# SpringReverbFront.net
KiCad netlist of a schematic drawn in EAGLE
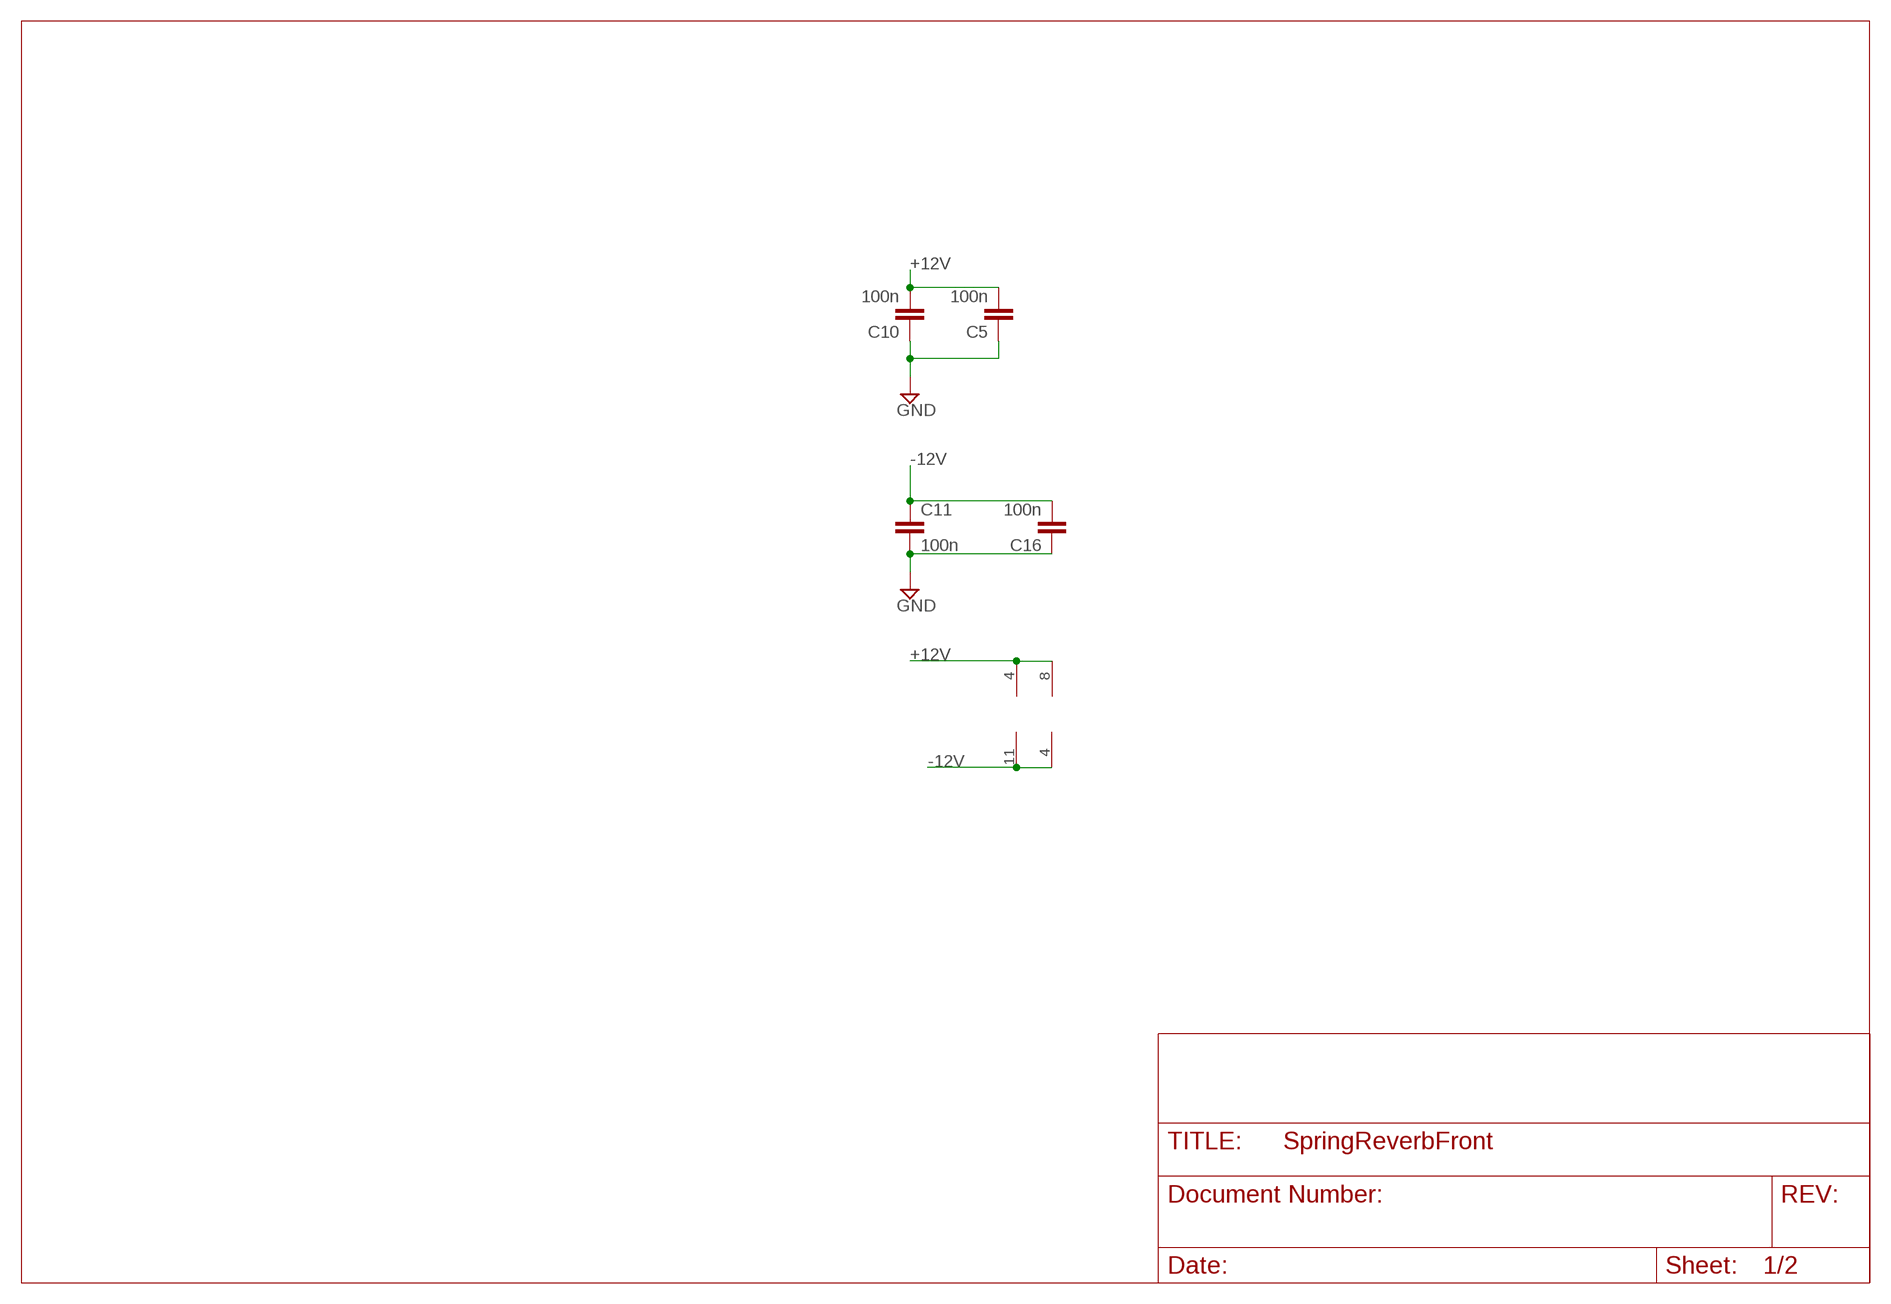
[diagram p0: schematic, sheet 1]
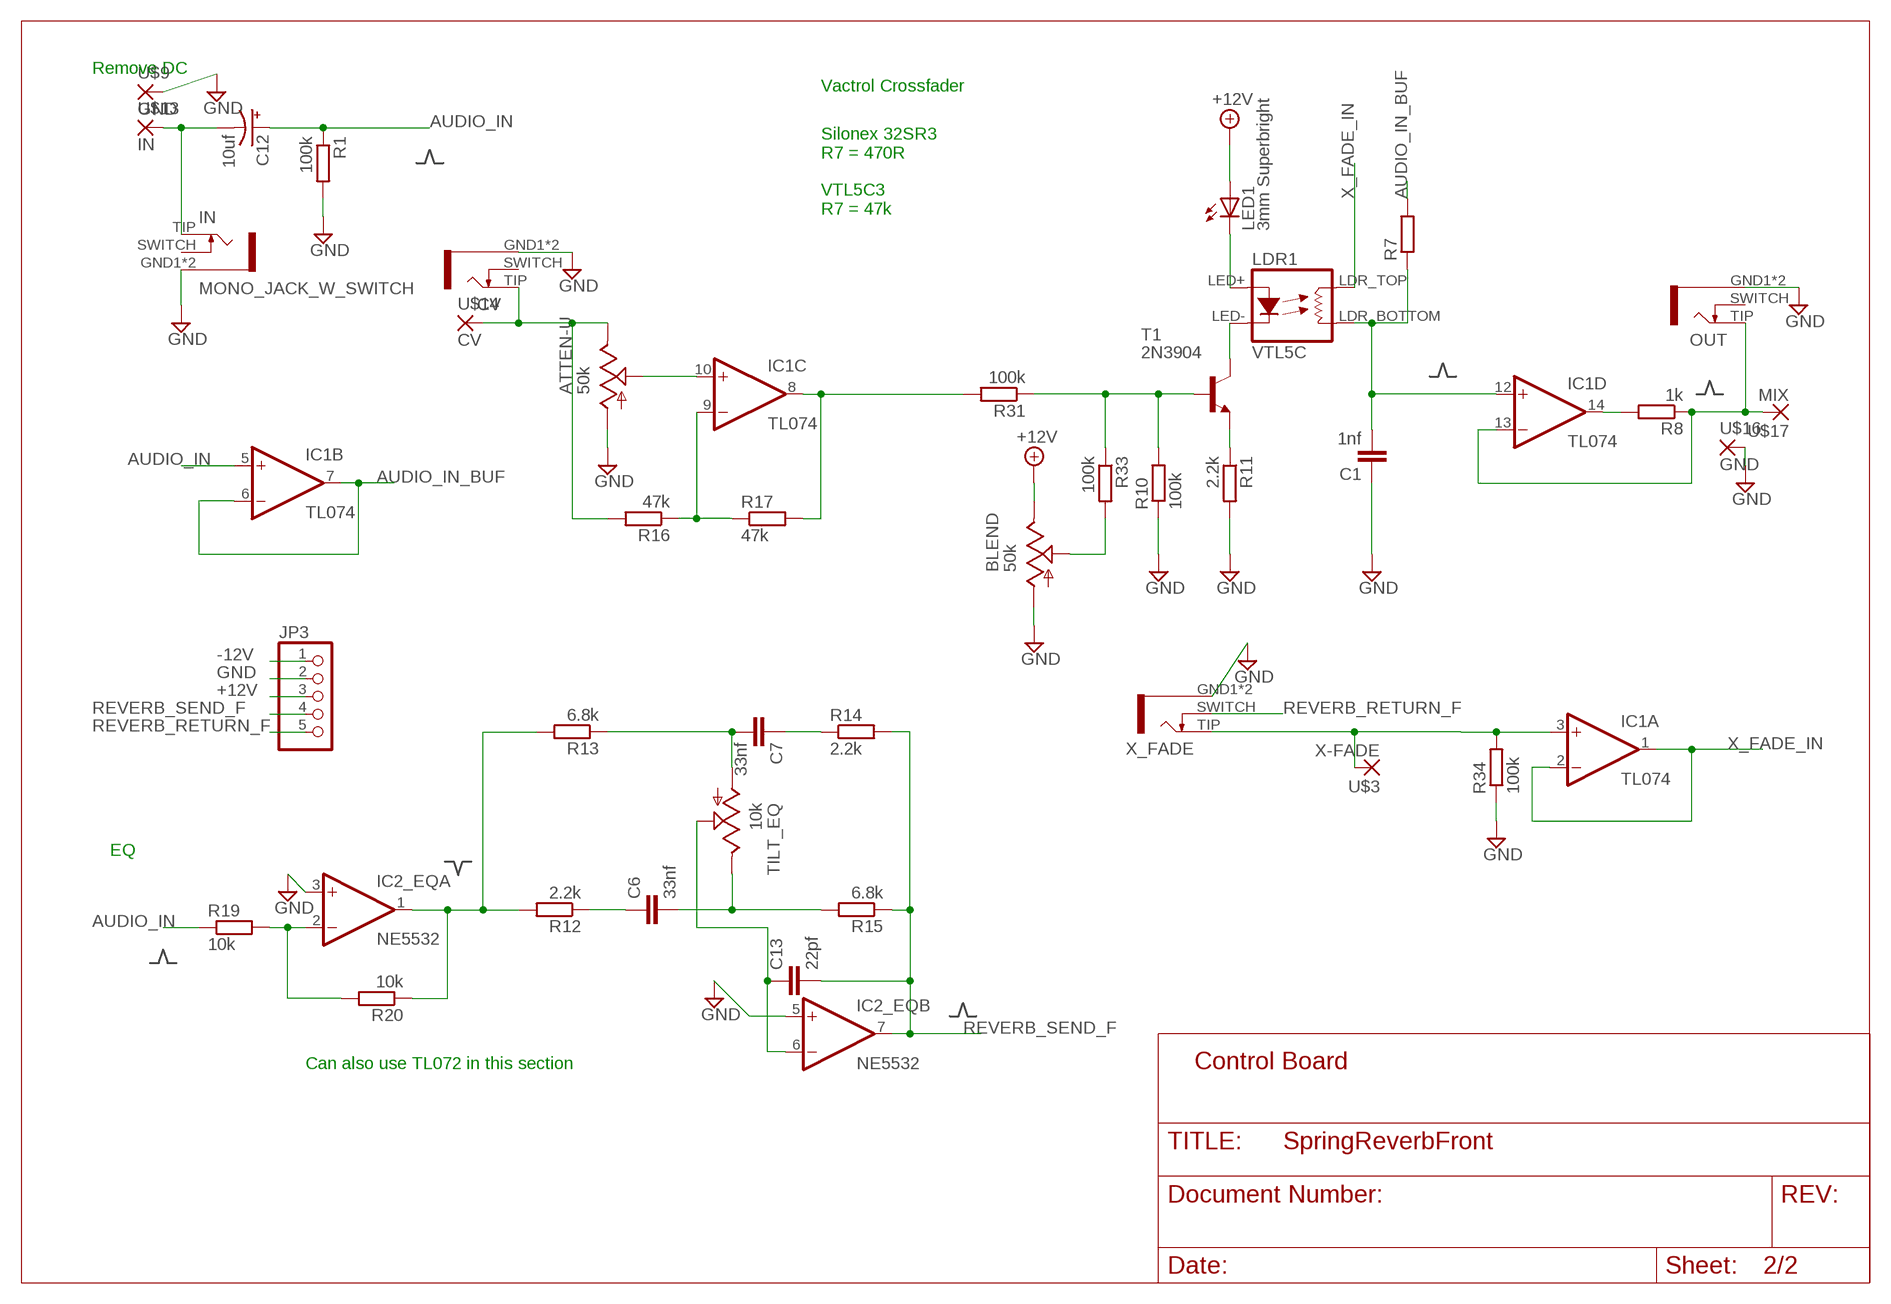
[diagram p1: schematic, sheet 2]

(export (version "E")
  (design (tool "Eeschema 10.0.6"))
  (components
    (comp (ref "ATTEN-U")
      (value "50k")
      (footprint "eagle-import:EVUF")
      (libsource (lib "eagle-import") (part "ALPHA-9MMAF2"))
    )
    (comp (ref "BLEND")
      (value "50k")
      (footprint "eagle-import:EVUF")
      (libsource (lib "eagle-import") (part "ALPHA-9MMAF2"))
    )
    (comp (ref "C1")
      (value "1nf")
      (footprint "eagle-import:C050-024X044")
      (libsource (lib "eagle-import") (part "C-EU050-024X044"))
    )
    (comp (ref "C6")
      (value "33nf")
      (footprint "eagle-import:C050-024X044")
      (libsource (lib "eagle-import") (part "C-EU050-024X044"))
    )
    (comp (ref "C7")
      (value "33nf")
      (footprint "eagle-import:C050-024X044")
      (libsource (lib "eagle-import") (part "C-EU050-024X044"))
    )
    (comp (ref "C12")
      (value "10uf")
      (footprint "eagle-import:050_020")
      (libsource (lib "eagle-import") (part "050"))
    )
    (comp (ref "C13")
      (value "22pf")
      (footprint "eagle-import:050X030_025")
      (libsource (lib "eagle-import") (part "050X030_0251"))
    )
    (comp (ref "CV")
      (value "MONO_JACK_W_SWITCH")
      (footprint "eagle-import:ERTHENVAR")
      (libsource (lib "eagle-import") (part "MONO_JACK_W_SWITCH"))
    )
    (comp (ref "IC1")
      (value "TL074")
      (footprint "eagle-import:DIL14")
      (libsource (lib "eagle-import") (part "TL074P"))
    )
    (comp (ref "IC2_EQ")
      (value "NE5532")
      (footprint "eagle-import:DIL08")
      (libsource (lib "eagle-import") (part "TL072P"))
    )
    (comp (ref "IN")
      (value "MONO_JACK_W_SWITCH")
      (footprint "eagle-import:ERTHENVAR")
      (libsource (lib "eagle-import") (part "MONO_JACK_W_SWITCH"))
    )
    (comp (ref "JP3")
      (value "PINHD-1X5")
      (footprint "eagle-import:1X05")
      (libsource (lib "eagle-import") (part "PINHD-1X5"))
    )
    (comp (ref "LDR1")
      (value "VTL5C")
      (footprint "eagle-import:VACTROL_COMPACT")
      (libsource (lib "eagle-import") (part "VACTROL_COMPACT"))
    )
    (comp (ref "LED1")
      (value "3mm Superbright")
      (footprint "eagle-import:LED3MM")
      (libsource (lib "eagle-import") (part "LED3MM"))
    )
    (comp (ref "OUT")
      (value "MONO_JACK_W_SWITCH")
      (footprint "eagle-import:ERTHENVAR")
      (libsource (lib "eagle-import") (part "MONO_JACK_W_SWITCH"))
    )
    (comp (ref "R1")
      (value "100k")
      (footprint "eagle-import:VERT-RESISTOR")
      (libsource (lib "eagle-import") (part "VERT-RESIST1"))
    )
    (comp (ref "R7")
      (value "R-EU_STANDARD_RESISTOR")
      (footprint "eagle-import:0207_10")
      (libsource (lib "eagle-import") (part "R-EU_STANDARD_RESISTOR"))
    )
    (comp (ref "R8")
      (value "1k")
      (footprint "eagle-import:0207_10")
      (libsource (lib "eagle-import") (part "R-EU_STANDARD_RESISTOR"))
    )
    (comp (ref "R10")
      (value "100k")
      (footprint "eagle-import:0207_10")
      (libsource (lib "eagle-import") (part "R-EU_STANDARD_RESISTOR"))
    )
    (comp (ref "R11")
      (value "2.2k")
      (footprint "eagle-import:0207_10")
      (libsource (lib "eagle-import") (part "R-EU_STANDARD_RESISTOR"))
    )
    (comp (ref "R12")
      (value "2.2k")
      (footprint "eagle-import:0207_10")
      (libsource (lib "eagle-import") (part "R-EU_STANDARD_RESISTOR"))
    )
    (comp (ref "R13")
      (value "6.8k")
      (footprint "eagle-import:0207_10")
      (libsource (lib "eagle-import") (part "R-EU_STANDARD_RESISTOR"))
    )
    (comp (ref "R14")
      (value "2.2k")
      (footprint "eagle-import:0207_10")
      (libsource (lib "eagle-import") (part "R-EU_STANDARD_RESISTOR"))
    )
    (comp (ref "R15")
      (value "6.8k")
      (footprint "eagle-import:0207_10")
      (libsource (lib "eagle-import") (part "R-EU_STANDARD_RESISTOR"))
    )
    (comp (ref "R16")
      (value "47k")
      (footprint "eagle-import:VERT-RESISTOR")
      (libsource (lib "eagle-import") (part "VERT-RESIST1"))
    )
    (comp (ref "R17")
      (value "47k")
      (footprint "eagle-import:VERT-RESISTOR")
      (libsource (lib "eagle-import") (part "VERT-RESIST1"))
    )
    (comp (ref "R19")
      (value "10k")
      (footprint "eagle-import:VERT-RESISTOR")
      (libsource (lib "eagle-import") (part "VERT-RESIST1"))
    )
    (comp (ref "R20")
      (value "10k")
      (footprint "eagle-import:0207_10")
      (libsource (lib "eagle-import") (part "R-EU_STANDARD_RESISTOR"))
    )
    (comp (ref "R31")
      (value "100k")
      (footprint "eagle-import:0207_10")
      (libsource (lib "eagle-import") (part "R-EU_STANDARD_RESISTOR"))
    )
    (comp (ref "R33")
      (value "100k")
      (footprint "eagle-import:0207_10")
      (libsource (lib "eagle-import") (part "R-EU_STANDARD_RESISTOR"))
    )
    (comp (ref "R34")
      (value "100k")
      (footprint "eagle-import:0207_10")
      (libsource (lib "eagle-import") (part "R-EU_STANDARD_RESISTOR"))
    )
    (comp (ref "T1")
      (value "2N3904")
      (footprint "eagle-import:TO92")
      (libsource (lib "eagle-import") (part "2N3904"))
    )
    (comp (ref "TILT_EQ")
      (value "10k")
      (footprint "eagle-import:EVUF")
      (libsource (lib "eagle-import") (part "ALPHA-9MMAF2"))
    )
    (comp (ref "U$3")
      (value "X-FADE")
      (footprint "eagle-import:LONG_PAD_1")
      (libsource (lib "eagle-import") (part "LONG_PAD_1"))
    )
    (comp (ref "U$9")
      (value "GND")
      (footprint "eagle-import:LONG_PAD_1")
      (libsource (lib "eagle-import") (part "LONG_PAD_1"))
    )
    (comp (ref "U$13")
      (value "IN")
      (footprint "eagle-import:LONG_PAD_1")
      (libsource (lib "eagle-import") (part "LONG_PAD_1"))
    )
    (comp (ref "U$14")
      (value "CV")
      (footprint "eagle-import:LONG_PAD_1")
      (libsource (lib "eagle-import") (part "LONG_PAD_1"))
    )
    (comp (ref "U$16")
      (value "GND")
      (footprint "eagle-import:LONG_PAD_1")
      (libsource (lib "eagle-import") (part "LONG_PAD_1"))
    )
    (comp (ref "U$17")
      (value "MIX")
      (footprint "eagle-import:LONG_PAD_1")
      (libsource (lib "eagle-import") (part "LONG_PAD_1"))
    )
    (comp (ref "X_FADE")
      (value "MONO_JACK_W_SWITCH")
      (footprint "eagle-import:ERTHENVAR")
      (libsource (lib "eagle-import") (part "MONO_JACK_W_SWITCH"))
    )
    (comp (ref "C5")
      (value "100n")
      (footprint "eagle-import:C050-024X044")
      (libsource (lib "eagle-import") (part "C-EU050-024X044"))
    )
    (comp (ref "C10")
      (value "100n")
      (footprint "eagle-import:C050-024X044")
      (libsource (lib "eagle-import") (part "C-EU050-024X044"))
    )
    (comp (ref "C11")
      (value "100n")
      (footprint "eagle-import:C050-024X044")
      (libsource (lib "eagle-import") (part "C-EU050-024X044"))
    )
    (comp (ref "C16")
      (value "100n")
      (footprint "eagle-import:C050-024X044")
      (libsource (lib "eagle-import") (part "C-EU050-024X044"))
    )
  )
  (nets
    (net (code "1") (name "+12V") (class "Default")
      (node (ref "BLEND") (pin "3") (pinfunction "E_3") (pintype "passive"))
      (node (ref "C10") (pin "2") (pinfunction "2_2") (pintype "passive"))
      (node (ref "C5") (pin "2") (pinfunction "2_2") (pintype "passive"))
      (node (ref "IC1") (pin "4") (pinfunction "V+_4") (pintype "power_in"))
      (node (ref "IC2_EQ") (pin "8") (pinfunction "V+_8") (pintype "power_in"))
      (node (ref "JP3") (pin "3") (pinfunction "3_3") (pintype "passive"))
      (node (ref "LED1") (pin "A") (pinfunction "A_A") (pintype "passive"))
    )
    (net (code "2") (name "-12V") (class "Default")
      (node (ref "C11") (pin "1") (pinfunction "1_1") (pintype "passive"))
      (node (ref "C16") (pin "2") (pinfunction "2_2") (pintype "passive"))
      (node (ref "IC1") (pin "11") (pinfunction "V-_11") (pintype "power_in"))
      (node (ref "IC2_EQ") (pin "4") (pinfunction "V-_4") (pintype "power_in"))
      (node (ref "JP3") (pin "1") (pinfunction "1_1") (pintype "passive"))
    )
    (net (code "3") (name "AUDIO_IN") (class "Default")
      (node (ref "C12") (pin "+") (pinfunction "+_+") (pintype "passive"))
      (node (ref "IC1") (pin "5") (pinfunction "+IN_5") (pintype "input"))
      (node (ref "R1") (pin "1") (pinfunction "1_1") (pintype "passive"))
      (node (ref "R19") (pin "1") (pinfunction "1_1") (pintype "passive"))
    )
    (net (code "4") (name "AUDIO_IN_BUF") (class "Default")
      (node (ref "IC1") (pin "6") (pinfunction "-IN_6") (pintype "input"))
      (node (ref "IC1") (pin "7") (pinfunction "OUT_7") (pintype "output"))
      (node (ref "R7") (pin "2") (pinfunction "2_2") (pintype "passive"))
    )
    (net (code "5") (name "GND") (class "Default")
      (node (ref "ATTEN-U") (pin "1") (pinfunction "A_1") (pintype "passive"))
      (node (ref "BLEND") (pin "1") (pinfunction "A_1") (pintype "passive"))
      (node (ref "C1") (pin "1") (pinfunction "1_1") (pintype "passive"))
      (node (ref "C10") (pin "1") (pinfunction "1_1") (pintype "passive"))
      (node (ref "C11") (pin "2") (pinfunction "2_2") (pintype "passive"))
      (node (ref "C16") (pin "1") (pinfunction "1_1") (pintype "passive"))
      (node (ref "C5") (pin "1") (pinfunction "1_1") (pintype "passive"))
      (node (ref "CV") (pin "GND1") (pinfunction "SLEEVE_GND1") (pintype "passive"))
      (node (ref "CV") (pin "GND2") (pinfunction "SLEEVE_GND2") (pintype "passive"))
      (node (ref "IC2_EQ") (pin "3") (pinfunction "+IN_3") (pintype "input"))
      (node (ref "IC2_EQ") (pin "5") (pinfunction "+IN_5") (pintype "input"))
      (node (ref "IN") (pin "GND1") (pinfunction "SLEEVE_GND1") (pintype "passive"))
      (node (ref "IN") (pin "GND2") (pinfunction "SLEEVE_GND2") (pintype "passive"))
      (node (ref "JP3") (pin "2") (pinfunction "2_2") (pintype "passive"))
      (node (ref "OUT") (pin "GND1") (pinfunction "SLEEVE_GND1") (pintype "passive"))
      (node (ref "OUT") (pin "GND2") (pinfunction "SLEEVE_GND2") (pintype "passive"))
      (node (ref "R1") (pin "2") (pinfunction "2_2") (pintype "passive"))
      (node (ref "R10") (pin "1") (pinfunction "1_1") (pintype "passive"))
      (node (ref "R11") (pin "2") (pinfunction "2_2") (pintype "passive"))
      (node (ref "R34") (pin "1") (pinfunction "1_1") (pintype "passive"))
      (node (ref "U$16") (pin "P$1") (pinfunction "P_P$1") (pintype "passive"))
      (node (ref "U$9") (pin "P$1") (pinfunction "P_P$1") (pintype "passive"))
      (node (ref "X_FADE") (pin "GND1") (pinfunction "SLEEVE_GND1") (pintype "passive"))
      (node (ref "X_FADE") (pin "GND2") (pinfunction "SLEEVE_GND2") (pintype "passive"))
    )
    (net (code "6") (name "Net-(ATTEN-U-E)") (class "Default")
      (node (ref "ATTEN-U") (pin "3") (pinfunction "E_3") (pintype "passive"))
      (node (ref "CV") (pin "TIP") (pinfunction "TIP_TIP") (pintype "passive"))
      (node (ref "R16") (pin "2") (pinfunction "2_2") (pintype "passive"))
      (node (ref "U$14") (pin "P$1") (pinfunction "P_P$1") (pintype "passive"))
    )
    (net (code "7") (name "Net-(ATTEN-U-S)") (class "Default")
      (node (ref "ATTEN-U") (pin "2") (pinfunction "S_2") (pintype "passive"))
      (node (ref "IC1") (pin "10") (pinfunction "+IN_10") (pintype "input"))
    )
    (net (code "8") (name "Net-(BLEND-S)") (class "Default")
      (node (ref "BLEND") (pin "2") (pinfunction "S_2") (pintype "passive"))
      (node (ref "R33") (pin "2") (pinfunction "2_2") (pintype "passive"))
    )
    (net (code "9") (name "Net-(C6-Pad1)") (class "Default")
      (node (ref "C6") (pin "1") (pinfunction "1_1") (pintype "passive"))
      (node (ref "R12") (pin "1") (pinfunction "1_1") (pintype "passive"))
    )
    (net (code "10") (name "Net-(C7-Pad1)") (class "Default")
      (node (ref "C7") (pin "1") (pinfunction "1_1") (pintype "passive"))
      (node (ref "R14") (pin "1") (pinfunction "1_1") (pintype "passive"))
    )
    (net (code "11") (name "Net-(IC1A-+IN)") (class "Default")
      (node (ref "IC1") (pin "3") (pinfunction "+IN_3") (pintype "input"))
      (node (ref "R34") (pin "2") (pinfunction "2_2") (pintype "passive"))
      (node (ref "U$3") (pin "P$1") (pinfunction "P_P$1") (pintype "passive"))
      (node (ref "X_FADE") (pin "TIP") (pinfunction "TIP_TIP") (pintype "passive"))
    )
    (net (code "12") (name "Net-(IC1C--IN)") (class "Default")
      (node (ref "IC1") (pin "9") (pinfunction "-IN_9") (pintype "input"))
      (node (ref "R16") (pin "1") (pinfunction "1_1") (pintype "passive"))
      (node (ref "R17") (pin "1") (pinfunction "1_1") (pintype "passive"))
    )
    (net (code "13") (name "Net-(IC1C-OUT)") (class "Default")
      (node (ref "IC1") (pin "8") (pinfunction "OUT_8") (pintype "output"))
      (node (ref "R17") (pin "2") (pinfunction "2_2") (pintype "passive"))
      (node (ref "R31") (pin "2") (pinfunction "2_2") (pintype "passive"))
    )
    (net (code "14") (name "Net-(IC1D-+IN)") (class "Default")
      (node (ref "C1") (pin "2") (pinfunction "2_2") (pintype "passive"))
      (node (ref "IC1") (pin "12") (pinfunction "+IN_12") (pintype "input"))
      (node (ref "LDR1") (pin "LDR_BOTTOM") (pinfunction "RES2_LDR_BOTTOM") (pintype "passive"))
      (node (ref "R7") (pin "1") (pinfunction "1_1") (pintype "passive"))
    )
    (net (code "15") (name "Net-(IC1D--IN)") (class "Default")
      (node (ref "IC1") (pin "13") (pinfunction "-IN_13") (pintype "input"))
      (node (ref "OUT") (pin "TIP") (pinfunction "TIP_TIP") (pintype "passive"))
      (node (ref "R8") (pin "1") (pinfunction "1_1") (pintype "passive"))
      (node (ref "U$17") (pin "P$1") (pinfunction "P_P$1") (pintype "passive"))
    )
    (net (code "16") (name "Net-(IC1D-OUT)") (class "Default")
      (node (ref "IC1") (pin "14") (pinfunction "OUT_14") (pintype "output"))
      (node (ref "R8") (pin "2") (pinfunction "2_2") (pintype "passive"))
    )
    (net (code "17") (name "Net-(IC2_EQA--IN)") (class "Default")
      (node (ref "IC2_EQ") (pin "2") (pinfunction "-IN_2") (pintype "input"))
      (node (ref "R19") (pin "2") (pinfunction "2_2") (pintype "passive"))
      (node (ref "R20") (pin "2") (pinfunction "2_2") (pintype "passive"))
    )
    (net (code "18") (name "Net-(IC2_EQA-OUT)") (class "Default")
      (node (ref "IC2_EQ") (pin "1") (pinfunction "OUT_1") (pintype "output"))
      (node (ref "R12") (pin "2") (pinfunction "2_2") (pintype "passive"))
      (node (ref "R13") (pin "2") (pinfunction "2_2") (pintype "passive"))
      (node (ref "R20") (pin "1") (pinfunction "1_1") (pintype "passive"))
    )
    (net (code "19") (name "Net-(IC2_EQB--IN)") (class "Default")
      (node (ref "C13") (pin "1") (pinfunction "1_1") (pintype "passive"))
      (node (ref "IC2_EQ") (pin "6") (pinfunction "-IN_6") (pintype "input"))
      (node (ref "TILT_EQ") (pin "2") (pinfunction "S_2") (pintype "passive"))
    )
    (net (code "20") (name "Net-(LED1-C)") (class "Default")
      (node (ref "LDR1") (pin "LED+") (pinfunction "LED+_LED+") (pintype "passive"))
      (node (ref "LED1") (pin "K") (pinfunction "C_K") (pintype "passive"))
    )
    (net (code "21") (name "Net-(T1-B)") (class "Default")
      (node (ref "R10") (pin "2") (pinfunction "2_2") (pintype "passive"))
      (node (ref "R31") (pin "1") (pinfunction "1_1") (pintype "passive"))
      (node (ref "R33") (pin "1") (pinfunction "1_1") (pintype "passive"))
      (node (ref "T1") (pin "2") (pinfunction "B_2") (pintype "passive"))
    )
    (net (code "22") (name "Net-(T1-C)") (class "Default")
      (node (ref "LDR1") (pin "LED-") (pinfunction "LED-_LED-") (pintype "passive"))
      (node (ref "T1") (pin "1") (pinfunction "C_1") (pintype "passive"))
    )
    (net (code "23") (name "Net-(T1-E)") (class "Default")
      (node (ref "R11") (pin "1") (pinfunction "1_1") (pintype "passive"))
      (node (ref "T1") (pin "3") (pinfunction "E_3") (pintype "passive"))
    )
    (net (code "24") (name "Net-(TILT_EQ-A)") (class "Default")
      (node (ref "C7") (pin "2") (pinfunction "2_2") (pintype "passive"))
      (node (ref "R13") (pin "1") (pinfunction "1_1") (pintype "passive"))
      (node (ref "TILT_EQ") (pin "1") (pinfunction "A_1") (pintype "passive"))
    )
    (net (code "25") (name "Net-(TILT_EQ-E)") (class "Default")
      (node (ref "C6") (pin "2") (pinfunction "2_2") (pintype "passive"))
      (node (ref "R15") (pin "2") (pinfunction "2_2") (pintype "passive"))
      (node (ref "TILT_EQ") (pin "3") (pinfunction "E_3") (pintype "passive"))
    )
    (net (code "26") (name "Net-(U$13-P)") (class "Default")
      (node (ref "C12") (pin "-") (pinfunction "-_-") (pintype "passive"))
      (node (ref "IN") (pin "TIP") (pinfunction "TIP_TIP") (pintype "passive"))
      (node (ref "U$13") (pin "P$1") (pinfunction "P_P$1") (pintype "passive"))
    )
    (net (code "27") (name "REVERB_RETURN_F") (class "Default")
      (node (ref "JP3") (pin "5") (pinfunction "5_5") (pintype "passive"))
      (node (ref "X_FADE") (pin "SWITCH") (pinfunction "SWITCH_SWITCH") (pintype "passive"))
    )
    (net (code "28") (name "REVERB_SEND_F") (class "Default")
      (node (ref "C13") (pin "2") (pinfunction "2_2") (pintype "passive"))
      (node (ref "IC2_EQ") (pin "7") (pinfunction "OUT_7") (pintype "output"))
      (node (ref "JP3") (pin "4") (pinfunction "4_4") (pintype "passive"))
      (node (ref "R14") (pin "2") (pinfunction "2_2") (pintype "passive"))
      (node (ref "R15") (pin "1") (pinfunction "1_1") (pintype "passive"))
    )
    (net (code "29") (name "X_FADE_IN") (class "Default")
      (node (ref "IC1") (pin "1") (pinfunction "OUT_1") (pintype "output"))
      (node (ref "IC1") (pin "2") (pinfunction "-IN_2") (pintype "input"))
      (node (ref "LDR1") (pin "LDR_TOP") (pinfunction "RES1_LDR_TOP") (pintype "passive"))
    )
    (net (code "30") (name "unconnected-(CV-PadSWITCH)") (class "Default")
      (node (ref "CV") (pin "SWITCH") (pinfunction "SWITCH_SWITCH") (pintype "passive"))
    )
    (net (code "31") (name "unconnected-(IN-PadSWITCH)") (class "Default")
      (node (ref "IN") (pin "SWITCH") (pinfunction "SWITCH_SWITCH") (pintype "passive"))
    )
    (net (code "32") (name "unconnected-(OUT-PadSWITCH)") (class "Default")
      (node (ref "OUT") (pin "SWITCH") (pinfunction "SWITCH_SWITCH") (pintype "passive"))
    )
  )
)
